# SignalProcessing.net
KiCad netlist of a schematic drawn in Altium Designer
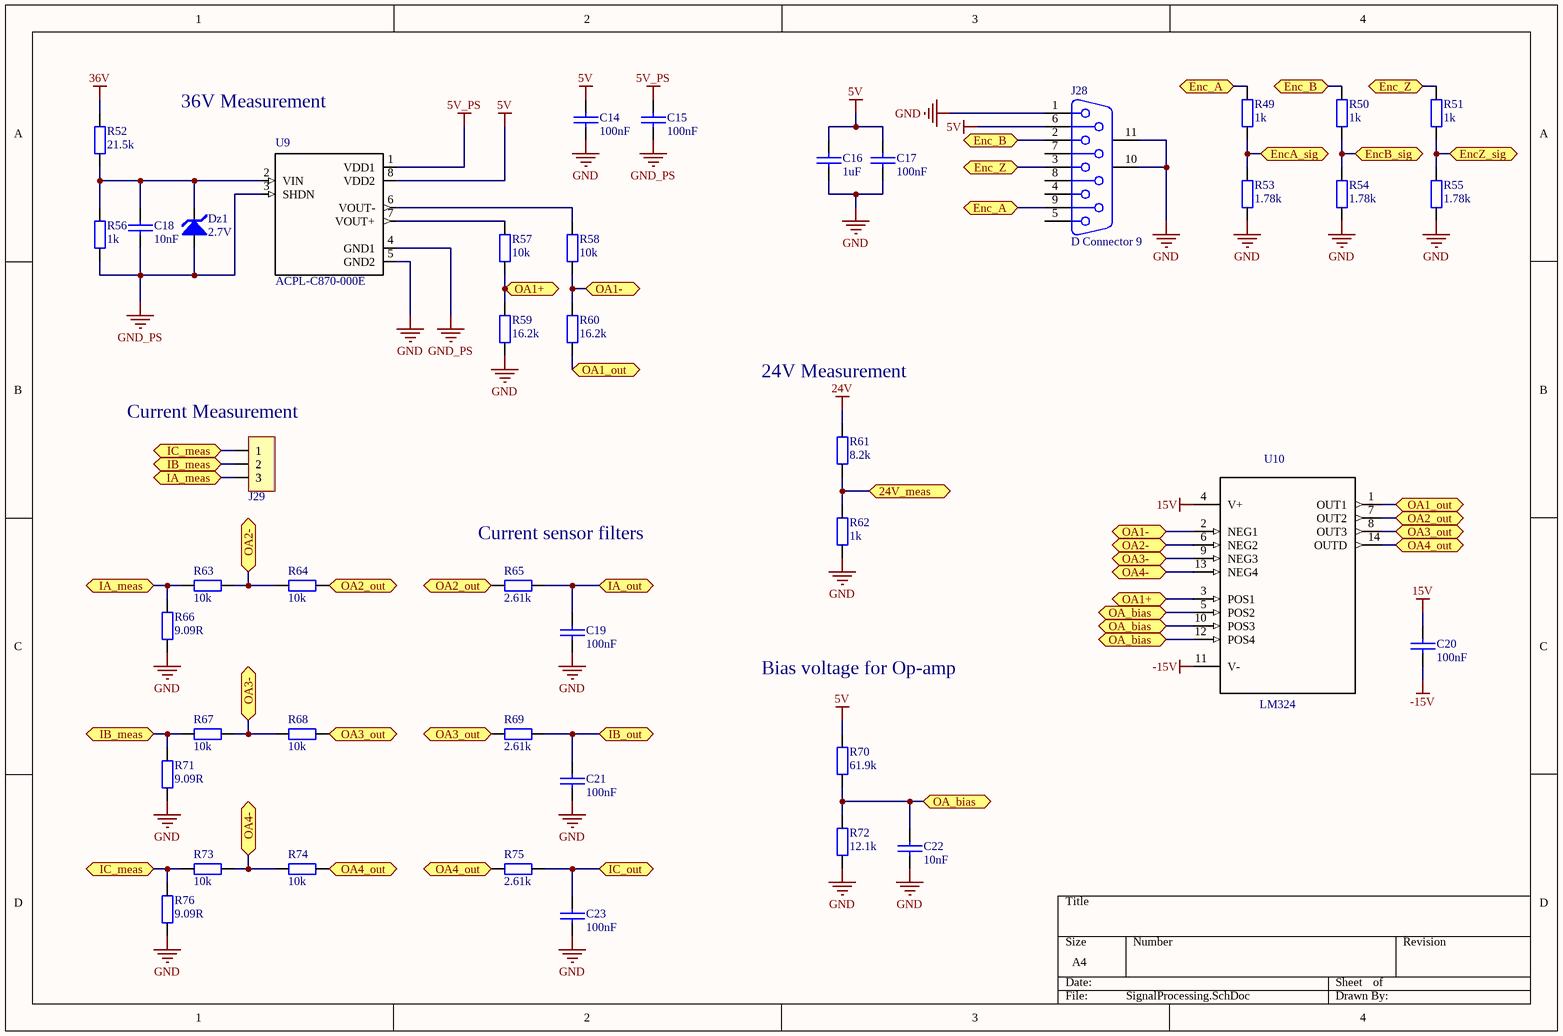
[diagram p0: SignalProcessing.SchDoc]

(export (version "E")
  (design (tool "Eeschema 10.0.6"))
  (components
    (comp (ref "C14")
      (value "100nF")
      (footprint "1206")
      (description "Condensador")
      (libsource (lib "SCH_Lib") (part "Condensador"))
    )
    (comp (ref "C15")
      (value "100nF")
      (footprint "1206")
      (description "Condensador")
      (libsource (lib "SCH_Lib") (part "Condensador"))
    )
    (comp (ref "C16")
      (value "1uF")
      (footprint "1206")
      (description "Condensador")
      (libsource (lib "SCH_Lib") (part "Condensador"))
    )
    (comp (ref "C17")
      (value "100nF")
      (footprint "1206")
      (description "Condensador")
      (libsource (lib "SCH_Lib") (part "Condensador"))
    )
    (comp (ref "C18")
      (value "10nF")
      (footprint "1206")
      (description "Condensador")
      (libsource (lib "SCH_Lib") (part "Condensador"))
    )
    (comp (ref "C19")
      (value "100nF")
      (footprint "1206")
      (description "Condensador")
      (libsource (lib "SCH_Lib") (part "Condensador"))
    )
    (comp (ref "C20")
      (value "100nF")
      (footprint "1206")
      (description "Condensador")
      (libsource (lib "SCH_Lib") (part "Condensador"))
    )
    (comp (ref "C21")
      (value "100nF")
      (footprint "1206")
      (description "Condensador")
      (libsource (lib "SCH_Lib") (part "Condensador"))
    )
    (comp (ref "C22")
      (value "10nF")
      (footprint "1206")
      (description "Condensador")
      (libsource (lib "SCH_Lib") (part "Condensador"))
    )
    (comp (ref "C23")
      (value "100nF")
      (footprint "1206")
      (description "Condensador")
      (libsource (lib "SCH_Lib") (part "Condensador"))
    )
    (comp (ref "Dz1") (value "2.7V") (footprint "Diodo") (libsource (lib "SCH_Lib") (part "Zener")))
    (comp (ref "J28")
      (value "D Connector 9")
      (footprint "DSUB1.385-2H9")
      (description "Receptacle Assembly, 9 Position, Right Angle")
      (fields (field (name "PUBLISHER") "Altium Limited"))
      (libsource (lib "Miscellaneous Connectors") (part "D Connector 9"))
    )
    (comp (ref "J29")
      (value "Cleva 2 vias")
      (footprint "Con3_KK_256")
      (libsource (lib "SCH_Lib") (part "Con_3"))
    )
    (comp (ref "R49")
      (value "1k")
      (footprint "1206")
      (description "Resistencia")
      (libsource (lib "SCH_Lib") (part "Resistencia"))
    )
    (comp (ref "R50")
      (value "1k")
      (footprint "1206")
      (description "Resistencia")
      (libsource (lib "SCH_Lib") (part "Resistencia"))
    )
    (comp (ref "R51")
      (value "1k")
      (footprint "1206")
      (description "Resistencia")
      (libsource (lib "SCH_Lib") (part "Resistencia"))
    )
    (comp (ref "R52")
      (value "21.5k")
      (footprint "1206")
      (description "Resistencia")
      (libsource (lib "SCH_Lib") (part "Resistencia"))
    )
    (comp (ref "R53")
      (value "1.78k")
      (footprint "1206")
      (description "Resistencia")
      (libsource (lib "SCH_Lib") (part "Resistencia"))
    )
    (comp (ref "R54")
      (value "1.78k")
      (footprint "1206")
      (description "Resistencia")
      (libsource (lib "SCH_Lib") (part "Resistencia"))
    )
    (comp (ref "R55")
      (value "1.78k")
      (footprint "1206")
      (description "Resistencia")
      (libsource (lib "SCH_Lib") (part "Resistencia"))
    )
    (comp (ref "R56")
      (value "1k")
      (footprint "1206")
      (description "Resistencia")
      (libsource (lib "SCH_Lib") (part "Resistencia"))
    )
    (comp (ref "R57")
      (value "10k")
      (footprint "1206")
      (description "Resistencia")
      (libsource (lib "SCH_Lib") (part "Resistencia"))
    )
    (comp (ref "R58")
      (value "10k")
      (footprint "1206")
      (description "Resistencia")
      (libsource (lib "SCH_Lib") (part "Resistencia"))
    )
    (comp (ref "R59")
      (value "16.2k")
      (footprint "1206")
      (description "Resistencia")
      (libsource (lib "SCH_Lib") (part "Resistencia"))
    )
    (comp (ref "R60")
      (value "16.2k")
      (footprint "1206")
      (description "Resistencia")
      (libsource (lib "SCH_Lib") (part "Resistencia"))
    )
    (comp (ref "R61")
      (value "8.2k")
      (footprint "1206")
      (description "Resistencia")
      (libsource (lib "SCH_Lib") (part "Resistencia"))
    )
    (comp (ref "R62")
      (value "1k")
      (footprint "1206")
      (description "Resistencia")
      (libsource (lib "SCH_Lib") (part "Resistencia"))
    )
    (comp (ref "R63")
      (value "10k")
      (footprint "1206")
      (description "Resistencia")
      (libsource (lib "SCH_Lib") (part "Resistencia"))
    )
    (comp (ref "R64")
      (value "10k")
      (footprint "1206")
      (description "Resistencia")
      (libsource (lib "SCH_Lib") (part "Resistencia"))
    )
    (comp (ref "R65")
      (value "2.61k")
      (footprint "1206")
      (description "Resistencia")
      (libsource (lib "SCH_Lib") (part "Resistencia"))
    )
    (comp (ref "R66")
      (value "9.09R")
      (footprint "1206")
      (description "Resistencia")
      (libsource (lib "SCH_Lib") (part "Resistencia"))
    )
    (comp (ref "R67")
      (value "10k")
      (footprint "1206")
      (description "Resistencia")
      (libsource (lib "SCH_Lib") (part "Resistencia"))
    )
    (comp (ref "R68")
      (value "10k")
      (footprint "1206")
      (description "Resistencia")
      (libsource (lib "SCH_Lib") (part "Resistencia"))
    )
    (comp (ref "R69")
      (value "2.61k")
      (footprint "1206")
      (description "Resistencia")
      (libsource (lib "SCH_Lib") (part "Resistencia"))
    )
    (comp (ref "R70")
      (value "61.9k")
      (footprint "1206")
      (description "Resistencia")
      (libsource (lib "SCH_Lib") (part "Resistencia"))
    )
    (comp (ref "R71")
      (value "9.09R")
      (footprint "1206")
      (description "Resistencia")
      (libsource (lib "SCH_Lib") (part "Resistencia"))
    )
    (comp (ref "R72")
      (value "12.1k")
      (footprint "1206")
      (description "Resistencia")
      (libsource (lib "SCH_Lib") (part "Resistencia"))
    )
    (comp (ref "R73")
      (value "10k")
      (footprint "1206")
      (description "Resistencia")
      (libsource (lib "SCH_Lib") (part "Resistencia"))
    )
    (comp (ref "R74")
      (value "10k")
      (footprint "1206")
      (description "Resistencia")
      (libsource (lib "SCH_Lib") (part "Resistencia"))
    )
    (comp (ref "R75")
      (value "2.61k")
      (footprint "1206")
      (description "Resistencia")
      (libsource (lib "SCH_Lib") (part "Resistencia"))
    )
    (comp (ref "R76")
      (value "9.09R")
      (footprint "1206")
      (description "Resistencia")
      (libsource (lib "SCH_Lib") (part "Resistencia"))
    )
    (comp (ref "U9")
      (value "ACPL-C870-000E")
      (footprint "SOIC127P1150X360-8N")
      (description "Isolation Amplifier [Broadcom] ACPL-C870-000E Isolation Amplifier")
      (fields (field (name "DIGI-KEY_PART_NUMBER") "516-2578-5-ND") (field (name "MF") "Broadcom Limited"))
      (libsource (lib "SCH_Lib") (part "ACPL-C870-000E"))
    )
    (comp (ref "U10")
      (value "LM324")
      (footprint "SOIC_14")
      (description "14 pin CMOS Quad Rail to Rail Input and Output Operational Amplifier 55 per tube")
      (fields (field (name "MP") "LMC6484IM") (field (name "MF") "Texas Instruments"))
      (libsource (lib "SCH_Lib") (part "LMC6484IM_1"))
    )
  )
  (nets
    (net (code "1") (name "-15V") (class "Default")
      (node (ref "C20") (pin "2") (pintype "passive"))
      (node (ref "U10") (pin "11") (pinfunction "V-_11") (pintype "power_in"))
    )
    (net (code "2") (name "/24V_meas") (class "Default")
      (node (ref "R61") (pin "2") (pinfunction "2_2") (pintype "passive"))
      (node (ref "R62") (pin "1") (pinfunction "1_1") (pintype "passive"))
    )
    (net (code "3") (name "/EncA_sig") (class "Default")
      (node (ref "R49") (pin "1") (pinfunction "1_1") (pintype "passive"))
      (node (ref "R53") (pin "2") (pinfunction "2_2") (pintype "passive"))
    )
    (net (code "4") (name "/EncB_sig") (class "Default")
      (node (ref "R50") (pin "1") (pinfunction "1_1") (pintype "passive"))
      (node (ref "R54") (pin "2") (pinfunction "2_2") (pintype "passive"))
    )
    (net (code "5") (name "/EncZ_sig") (class "Default")
      (node (ref "R51") (pin "1") (pinfunction "1_1") (pintype "passive"))
      (node (ref "R55") (pin "2") (pinfunction "2_2") (pintype "passive"))
    )
    (net (code "6") (name "/Enc_A") (class "Default")
      (node (ref "J28") (pin "9") (pinfunction "9_9") (pintype "passive"))
      (node (ref "R49") (pin "2") (pinfunction "2_2") (pintype "passive"))
    )
    (net (code "7") (name "/Enc_B") (class "Default")
      (node (ref "J28") (pin "2") (pinfunction "2_2") (pintype "passive"))
      (node (ref "R50") (pin "2") (pinfunction "2_2") (pintype "passive"))
    )
    (net (code "8") (name "/Enc_Z") (class "Default")
      (node (ref "J28") (pin "3") (pinfunction "3_3") (pintype "passive"))
      (node (ref "R51") (pin "2") (pinfunction "2_2") (pintype "passive"))
    )
    (net (code "9") (name "/IA_meas") (class "Default")
      (node (ref "J29") (pin "3") (pinfunction "3_3") (pintype "passive"))
      (node (ref "R63") (pin "1") (pinfunction "1_1") (pintype "passive"))
      (node (ref "R66") (pin "1") (pinfunction "1_1") (pintype "passive"))
    )
    (net (code "10") (name "/IA_out") (class "Default")
      (node (ref "C19") (pin "1") (pintype "passive"))
      (node (ref "R65") (pin "2") (pinfunction "2_2") (pintype "passive"))
    )
    (net (code "11") (name "/IB_meas") (class "Default")
      (node (ref "J29") (pin "2") (pinfunction "2_2") (pintype "passive"))
      (node (ref "R67") (pin "1") (pinfunction "1_1") (pintype "passive"))
      (node (ref "R71") (pin "1") (pinfunction "1_1") (pintype "passive"))
    )
    (net (code "12") (name "/IB_out") (class "Default")
      (node (ref "C21") (pin "1") (pintype "passive"))
      (node (ref "R69") (pin "2") (pinfunction "2_2") (pintype "passive"))
    )
    (net (code "13") (name "/IC_meas") (class "Default")
      (node (ref "J29") (pin "1") (pinfunction "1_1") (pintype "passive"))
      (node (ref "R73") (pin "1") (pinfunction "1_1") (pintype "passive"))
      (node (ref "R76") (pin "1") (pinfunction "1_1") (pintype "passive"))
    )
    (net (code "14") (name "/IC_out") (class "Default")
      (node (ref "C23") (pin "1") (pintype "passive"))
      (node (ref "R75") (pin "2") (pinfunction "2_2") (pintype "passive"))
    )
    (net (code "15") (name "/OA1+") (class "Default")
      (node (ref "R57") (pin "2") (pinfunction "2_2") (pintype "passive"))
      (node (ref "R59") (pin "1") (pinfunction "1_1") (pintype "passive"))
      (node (ref "U10") (pin "3") (pinfunction "POS1_3") (pintype "input"))
    )
    (net (code "16") (name "/OA1-") (class "Default")
      (node (ref "R58") (pin "1") (pinfunction "1_1") (pintype "passive"))
      (node (ref "R60") (pin "1") (pinfunction "1_1") (pintype "passive"))
      (node (ref "U10") (pin "2") (pinfunction "NEG1_2") (pintype "input"))
    )
    (net (code "17") (name "/OA1_out") (class "Default")
      (node (ref "R60") (pin "2") (pinfunction "2_2") (pintype "passive"))
      (node (ref "U10") (pin "1") (pinfunction "OUT1_1") (pintype "output"))
    )
    (net (code "18") (name "/OA2-") (class "Default")
      (node (ref "R63") (pin "2") (pinfunction "2_2") (pintype "passive"))
      (node (ref "R64") (pin "1") (pinfunction "1_1") (pintype "passive"))
      (node (ref "U10") (pin "6") (pinfunction "NEG2_6") (pintype "input"))
    )
    (net (code "19") (name "/OA2_out") (class "Default")
      (node (ref "R64") (pin "2") (pinfunction "2_2") (pintype "passive"))
      (node (ref "R65") (pin "1") (pinfunction "1_1") (pintype "passive"))
      (node (ref "U10") (pin "7") (pinfunction "OUT2_7") (pintype "output"))
    )
    (net (code "20") (name "/OA3-") (class "Default")
      (node (ref "R67") (pin "2") (pinfunction "2_2") (pintype "passive"))
      (node (ref "R68") (pin "1") (pinfunction "1_1") (pintype "passive"))
      (node (ref "U10") (pin "9") (pinfunction "NEG3_9") (pintype "input"))
    )
    (net (code "21") (name "/OA3_out") (class "Default")
      (node (ref "R68") (pin "2") (pinfunction "2_2") (pintype "passive"))
      (node (ref "R69") (pin "1") (pinfunction "1_1") (pintype "passive"))
      (node (ref "U10") (pin "8") (pinfunction "OUT3_8") (pintype "output"))
    )
    (net (code "22") (name "/OA4-") (class "Default")
      (node (ref "R73") (pin "2") (pinfunction "2_2") (pintype "passive"))
      (node (ref "R74") (pin "1") (pinfunction "1_1") (pintype "passive"))
      (node (ref "U10") (pin "13") (pinfunction "NEG4_13") (pintype "input"))
    )
    (net (code "23") (name "/OA4_out") (class "Default")
      (node (ref "R74") (pin "2") (pinfunction "2_2") (pintype "passive"))
      (node (ref "R75") (pin "1") (pinfunction "1_1") (pintype "passive"))
      (node (ref "U10") (pin "14") (pinfunction "OUTD_14") (pintype "output"))
    )
    (net (code "24") (name "/OA_bias") (class "Default")
      (node (ref "C22") (pin "1") (pintype "passive"))
      (node (ref "R70") (pin "1") (pinfunction "1_1") (pintype "passive"))
      (node (ref "R72") (pin "2") (pinfunction "2_2") (pintype "passive"))
      (node (ref "U10") (pin "10") (pinfunction "POS3_10") (pintype "input"))
      (node (ref "U10") (pin "12") (pinfunction "POS4_12") (pintype "input"))
      (node (ref "U10") (pin "5") (pinfunction "POS2_5") (pintype "input"))
    )
    (net (code "25") (name "5V") (class "Default")
      (node (ref "C14") (pin "1") (pintype "passive"))
      (node (ref "C16") (pin "1") (pintype "passive"))
      (node (ref "C17") (pin "1") (pintype "passive"))
      (node (ref "J28") (pin "6") (pinfunction "6_6") (pintype "passive"))
      (node (ref "R70") (pin "2") (pinfunction "2_2") (pintype "passive"))
      (node (ref "U9") (pin "8") (pinfunction "VDD2_8") (pintype "power_in"))
    )
    (net (code "26") (name "5V_PS") (class "Default")
      (node (ref "C15") (pin "1") (pintype "passive"))
      (node (ref "U9") (pin "1") (pinfunction "VDD1_1") (pintype "power_in"))
    )
    (net (code "27") (name "15V") (class "Default")
      (node (ref "C20") (pin "1") (pintype "passive"))
      (node (ref "U10") (pin "4") (pinfunction "V+_4") (pintype "power_in"))
    )
    (net (code "28") (name "24V") (class "Default")
      (node (ref "R61") (pin "1") (pinfunction "1_1") (pintype "passive"))
    )
    (net (code "29") (name "36V") (class "Default")
      (node (ref "R52") (pin "1") (pinfunction "1_1") (pintype "passive"))
    )
    (net (code "30") (name "GND") (class "Default")
      (node (ref "C14") (pin "2") (pintype "passive"))
      (node (ref "C16") (pin "2") (pintype "passive"))
      (node (ref "C17") (pin "2") (pintype "passive"))
      (node (ref "C19") (pin "2") (pintype "passive"))
      (node (ref "C21") (pin "2") (pintype "passive"))
      (node (ref "C22") (pin "2") (pintype "passive"))
      (node (ref "C23") (pin "2") (pintype "passive"))
      (node (ref "J28") (pin "1") (pinfunction "1_1") (pintype "passive"))
      (node (ref "J28") (pin "10") (pinfunction "MH1_10") (pintype "passive"))
      (node (ref "J28") (pin "11") (pinfunction "MH2_11") (pintype "passive"))
      (node (ref "R53") (pin "1") (pinfunction "1_1") (pintype "passive"))
      (node (ref "R54") (pin "1") (pinfunction "1_1") (pintype "passive"))
      (node (ref "R55") (pin "1") (pinfunction "1_1") (pintype "passive"))
      (node (ref "R59") (pin "2") (pinfunction "2_2") (pintype "passive"))
      (node (ref "R62") (pin "2") (pinfunction "2_2") (pintype "passive"))
      (node (ref "R66") (pin "2") (pinfunction "2_2") (pintype "passive"))
      (node (ref "R71") (pin "2") (pinfunction "2_2") (pintype "passive"))
      (node (ref "R72") (pin "1") (pinfunction "1_1") (pintype "passive"))
      (node (ref "R76") (pin "2") (pinfunction "2_2") (pintype "passive"))
      (node (ref "U9") (pin "5") (pinfunction "GND2_5") (pintype "power_in"))
    )
    (net (code "31") (name "GND_PS") (class "Default")
      (node (ref "C15") (pin "2") (pintype "passive"))
      (node (ref "C18") (pin "2") (pintype "passive"))
      (node (ref "Dz1") (pin "1") (pinfunction "A_1") (pintype "passive"))
      (node (ref "R56") (pin "2") (pinfunction "2_2") (pintype "passive"))
      (node (ref "U9") (pin "3") (pinfunction "SHDN_3") (pintype "input"))
      (node (ref "U9") (pin "4") (pinfunction "GND1_4") (pintype "power_in"))
    )
    (net (code "32") (name "Net-(Dz1-K)") (class "Default")
      (node (ref "C18") (pin "1") (pintype "passive"))
      (node (ref "Dz1") (pin "2") (pinfunction "K_2") (pintype "passive"))
      (node (ref "R52") (pin "2") (pinfunction "2_2") (pintype "passive"))
      (node (ref "R56") (pin "1") (pinfunction "1_1") (pintype "passive"))
      (node (ref "U9") (pin "2") (pinfunction "VIN_2") (pintype "input"))
    )
    (net (code "33") (name "Net-(U9-VOUT+)") (class "Default")
      (node (ref "R57") (pin "1") (pinfunction "1_1") (pintype "passive"))
      (node (ref "U9") (pin "7") (pinfunction "VOUT+_7") (pintype "output"))
    )
    (net (code "34") (name "Net-(U9-VOUT-)") (class "Default")
      (node (ref "R58") (pin "2") (pinfunction "2_2") (pintype "passive"))
      (node (ref "U9") (pin "6") (pinfunction "VOUT-_6") (pintype "output"))
    )
    (net (code "35") (name "unconnected-(J28-Pad4)") (class "Default")
      (node (ref "J28") (pin "4") (pinfunction "4_4") (pintype "passive"))
    )
    (net (code "36") (name "unconnected-(J28-Pad5)") (class "Default")
      (node (ref "J28") (pin "5") (pinfunction "5_5") (pintype "passive"))
    )
    (net (code "37") (name "unconnected-(J28-Pad7)") (class "Default")
      (node (ref "J28") (pin "7") (pinfunction "7_7") (pintype "passive"))
    )
    (net (code "38") (name "unconnected-(J28-Pad8)") (class "Default")
      (node (ref "J28") (pin "8") (pinfunction "8_8") (pintype "passive"))
    )
  )
)
